# bandswitch.net
KiCad netlist of a schematic drawn in EAGLE
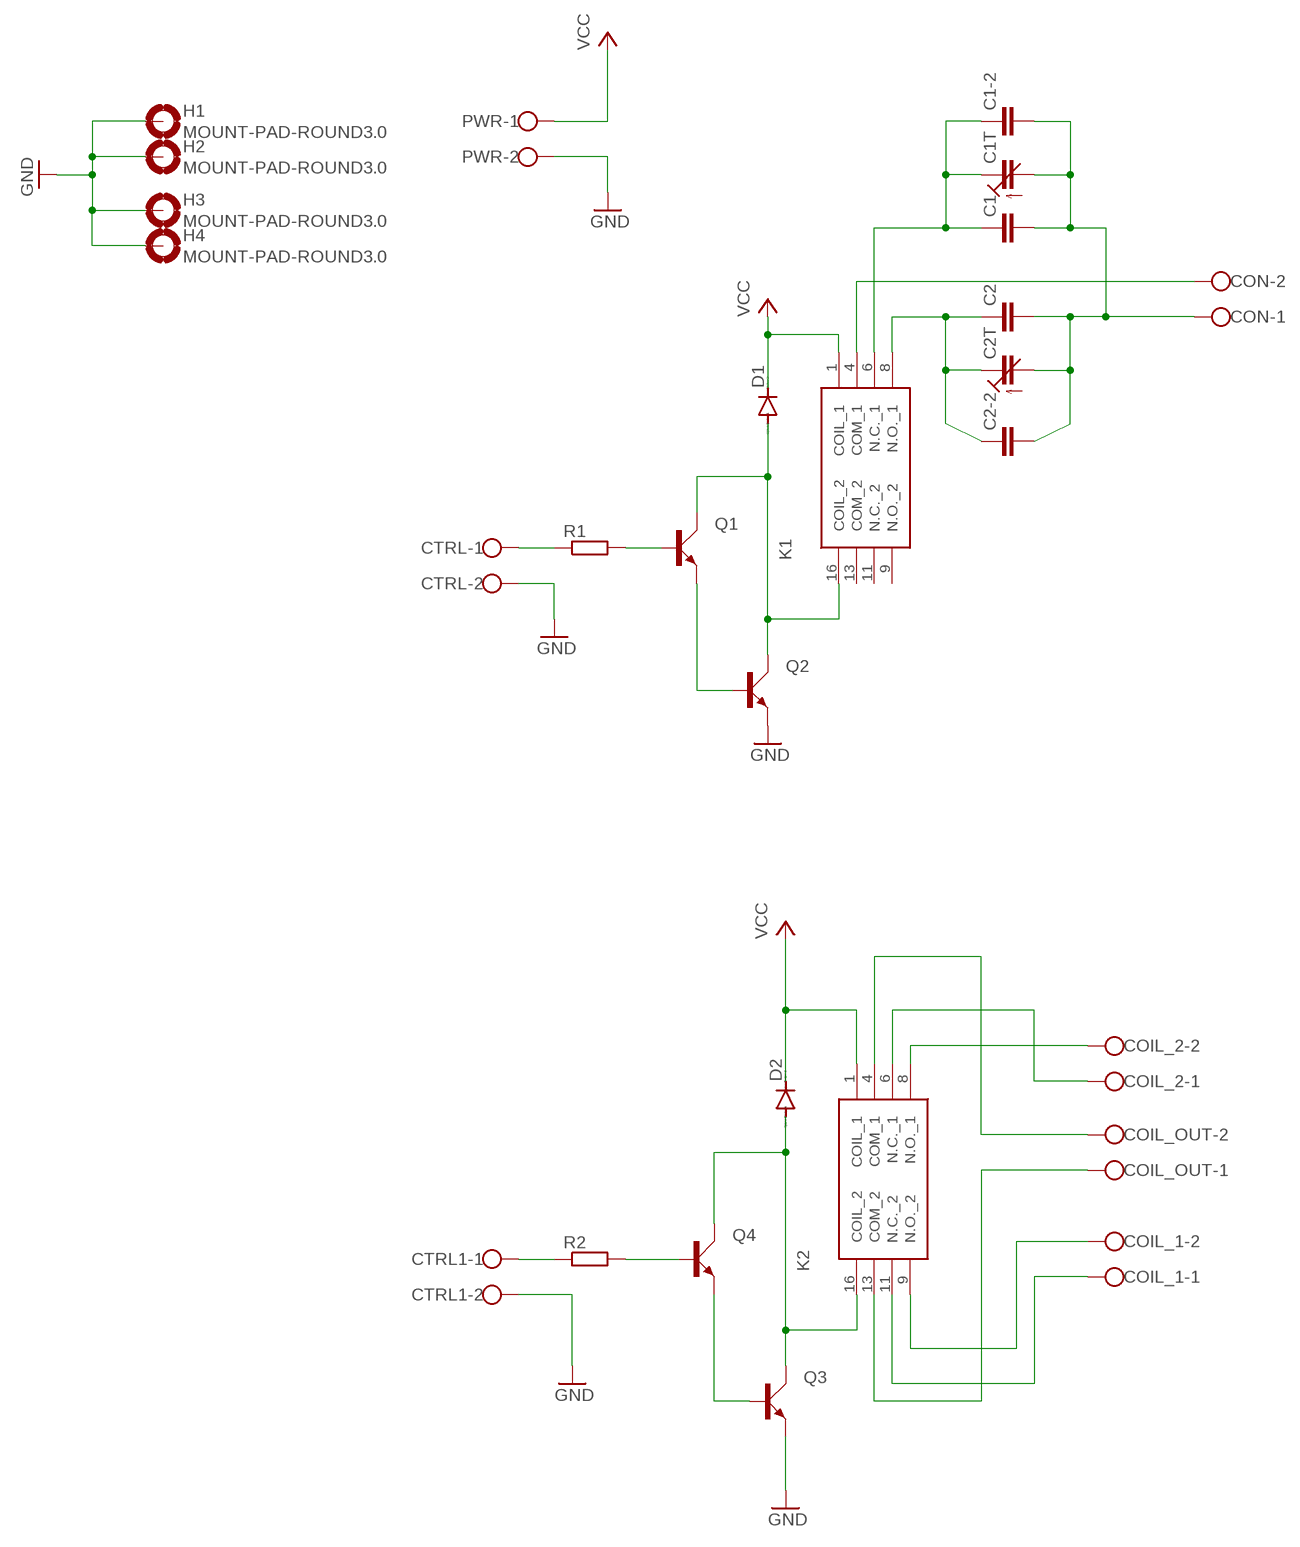
[diagram p0: schematic, sheet 1]

(export (version "E")
  (design (tool "Eeschema 10.0.6"))
  (components
    (comp (ref "C1")
      (value "C_0805_PTH")
      (footprint "eagle-import:C0805K")
      (libsource (lib "eagle-import") (part "C_0805_PTH"))
    )
    (comp (ref "C1-2")
      (value "C_0805_PTH")
      (footprint "eagle-import:C0805K")
      (libsource (lib "eagle-import") (part "C_0805_PTH"))
    )
    (comp (ref "C1T")
      (value "C_TRIM_TH")
      (footprint "eagle-import:CTRIM3050.505")
      (libsource (lib "eagle-import") (part "C_TRIM_TH"))
    )
    (comp (ref "C2")
      (value "C_0805_PTH")
      (footprint "eagle-import:C0805K")
      (libsource (lib "eagle-import") (part "C_0805_PTH"))
    )
    (comp (ref "C2-2")
      (value "C_0805_PTH")
      (footprint "eagle-import:C0805K")
      (libsource (lib "eagle-import") (part "C_0805_PTH"))
    )
    (comp (ref "C2T")
      (value "C_TRIM_TH")
      (footprint "eagle-import:CTRIM3050.505")
      (libsource (lib "eagle-import") (part "C_TRIM_TH"))
    )
    (comp (ref "COIL_1")
      (value "W237-102")
      (footprint "eagle-import:W237-102")
      (fields (field (name "MPN") "237-102"))
      (libsource (lib "eagle-import") (part "W237-102"))
    )
    (comp (ref "COIL_2")
      (value "W237-102")
      (footprint "eagle-import:W237-102")
      (fields (field (name "MPN") "237-102"))
      (libsource (lib "eagle-import") (part "W237-102"))
    )
    (comp (ref "COIL_OUT")
      (value "W237-102")
      (footprint "eagle-import:W237-102")
      (fields (field (name "MPN") "237-102"))
      (libsource (lib "eagle-import") (part "W237-102"))
    )
    (comp (ref "CON")
      (value "W237-102")
      (footprint "eagle-import:W237-102")
      (fields (field (name "MPN") "237-102"))
      (libsource (lib "eagle-import") (part "W237-102"))
    )
    (comp (ref "CTRL")
      (value "W237-102")
      (footprint "eagle-import:W237-102")
      (fields (field (name "MPN") "237-102"))
      (libsource (lib "eagle-import") (part "W237-102"))
    )
    (comp (ref "CTRL1")
      (value "W237-102")
      (footprint "eagle-import:W237-102")
      (fields (field (name "MPN") "237-102"))
      (libsource (lib "eagle-import") (part "W237-102"))
    )
    (comp (ref "D1")
      (value "1N4148DO35-7")
      (footprint "eagle-import:DO35-7")
      (libsource (lib "eagle-import") (part "1N4148DO35-7"))
    )
    (comp (ref "D2")
      (value "1N4148DO35-7")
      (footprint "eagle-import:DO35-7")
      (libsource (lib "eagle-import") (part "1N4148DO35-7"))
    )
    (comp (ref "H1")
      (value "MOUNT-PAD-ROUND3.0")
      (footprint "eagle-import:3,0-PAD")
      (libsource (lib "eagle-import") (part "MOUNT-PAD-ROUND3.0"))
    )
    (comp (ref "H2")
      (value "MOUNT-PAD-ROUND3.0")
      (footprint "eagle-import:3,0-PAD")
      (libsource (lib "eagle-import") (part "MOUNT-PAD-ROUND3.0"))
    )
    (comp (ref "H3")
      (value "MOUNT-PAD-ROUND3.0")
      (footprint "eagle-import:3,0-PAD")
      (libsource (lib "eagle-import") (part "MOUNT-PAD-ROUND3.0"))
    )
    (comp (ref "H4")
      (value "MOUNT-PAD-ROUND3.0")
      (footprint "eagle-import:3,0-PAD")
      (libsource (lib "eagle-import") (part "MOUNT-PAD-ROUND3.0"))
    )
    (comp (ref "K1")
      (value "G5V-2-H1-DC5")
      (footprint "eagle-import:G5V2H1DC5")
      (fields (field (name "MOUSER_PART_NUMBER") "653-G5V-2-H1-DC5"))
      (libsource (lib "eagle-import") (part "G5V-2-H1-DC5"))
    )
    (comp (ref "K2")
      (value "G5V-2-H1-DC5")
      (footprint "eagle-import:G5V2H1DC5")
      (fields (field (name "MOUSER_PART_NUMBER") "653-G5V-2-H1-DC5"))
      (libsource (lib "eagle-import") (part "G5V-2-H1-DC5"))
    )
    (comp (ref "PWR")
      (value "W237-102")
      (footprint "eagle-import:W237-102")
      (fields (field (name "MPN") "237-102"))
      (libsource (lib "eagle-import") (part "W237-102"))
    )
    (comp (ref "Q1")
      (value "BC547")
      (footprint "eagle-import:SOT54A")
      (libsource (lib "eagle-import") (part "BC547"))
    )
    (comp (ref "Q2")
      (value "BC547")
      (footprint "eagle-import:SOT54A")
      (libsource (lib "eagle-import") (part "BC547"))
    )
    (comp (ref "Q3")
      (value "BC547")
      (footprint "eagle-import:SOT54A")
      (libsource (lib "eagle-import") (part "BC547"))
    )
    (comp (ref "Q4")
      (value "BC547")
      (footprint "eagle-import:SOT54A")
      (libsource (lib "eagle-import") (part "BC547"))
    )
    (comp (ref "R1")
      (value "R_0805_PTH")
      (footprint "eagle-import:R0805")
      (libsource (lib "eagle-import") (part "R_0805_PTH"))
    )
    (comp (ref "R2")
      (value "R_0805_PTH")
      (footprint "eagle-import:R0805")
      (libsource (lib "eagle-import") (part "R_0805_PTH"))
    )
  )
  (nets
    (net (code "1") (name "GND") (class "Default")
      (node (ref "CTRL") (pin "2") (pinfunction "KL_2") (pintype "passive"))
      (node (ref "CTRL1") (pin "2") (pinfunction "KL_2") (pintype "passive"))
      (node (ref "H1") (pin "B3,0") (pinfunction "MOUNT_B3,0") (pintype "passive"))
      (node (ref "H2") (pin "B3,0") (pinfunction "MOUNT_B3,0") (pintype "passive"))
      (node (ref "H3") (pin "B3,0") (pinfunction "MOUNT_B3,0") (pintype "passive"))
      (node (ref "H4") (pin "B3,0") (pinfunction "MOUNT_B3,0") (pintype "passive"))
      (node (ref "PWR") (pin "2") (pinfunction "KL_2") (pintype "passive"))
      (node (ref "Q2") (pin "E") (pinfunction "E_E") (pintype "passive"))
      (node (ref "Q3") (pin "E") (pinfunction "E_E") (pintype "passive"))
    )
    (net (code "2") (name "Net-(C1T-A)") (class "Default")
      (node (ref "C1") (pin "2") (pinfunction "2_2") (pintype "passive"))
      (node (ref "C1") (pin "P$2") (pinfunction "2_P$2") (pintype "passive"))
      (node (ref "C1-2") (pin "2") (pinfunction "2_2") (pintype "passive"))
      (node (ref "C1-2") (pin "P$2") (pinfunction "2_P$2") (pintype "passive"))
      (node (ref "C1T") (pin "1") (pinfunction "A_1") (pintype "passive"))
      (node (ref "C2") (pin "2") (pinfunction "2_2") (pintype "passive"))
      (node (ref "C2") (pin "P$2") (pinfunction "2_P$2") (pintype "passive"))
      (node (ref "C2-2") (pin "2") (pinfunction "2_2") (pintype "passive"))
      (node (ref "C2-2") (pin "P$2") (pinfunction "2_P$2") (pintype "passive"))
      (node (ref "C2T") (pin "1") (pinfunction "A_1") (pintype "passive"))
      (node (ref "CON") (pin "1") (pinfunction "KL_1") (pintype "passive"))
    )
    (net (code "3") (name "Net-(C1T-E)") (class "Default")
      (node (ref "C1") (pin "1") (pinfunction "1_1") (pintype "passive"))
      (node (ref "C1") (pin "P$1") (pinfunction "1_P$1") (pintype "passive"))
      (node (ref "C1-2") (pin "1") (pinfunction "1_1") (pintype "passive"))
      (node (ref "C1-2") (pin "P$1") (pinfunction "1_P$1") (pintype "passive"))
      (node (ref "C1T") (pin "2") (pinfunction "E_2") (pintype "passive"))
      (node (ref "K1") (pin "6") (pinfunction "N.C._1_6") (pintype "bidirectional"))
    )
    (net (code "4") (name "Net-(C2T-E)") (class "Default")
      (node (ref "C2") (pin "1") (pinfunction "1_1") (pintype "passive"))
      (node (ref "C2") (pin "P$1") (pinfunction "1_P$1") (pintype "passive"))
      (node (ref "C2-2") (pin "1") (pinfunction "1_1") (pintype "passive"))
      (node (ref "C2-2") (pin "P$1") (pinfunction "1_P$1") (pintype "passive"))
      (node (ref "C2T") (pin "2") (pinfunction "E_2") (pintype "passive"))
      (node (ref "K1") (pin "8") (pinfunction "N.O._1_8") (pintype "bidirectional"))
    )
    (net (code "5") (name "Net-(COIL_1A-KL)") (class "Default")
      (node (ref "COIL_1") (pin "1") (pinfunction "KL_1") (pintype "passive"))
      (node (ref "K2") (pin "11") (pinfunction "N.C._2_11") (pintype "bidirectional"))
    )
    (net (code "6") (name "Net-(COIL_1B-KL)") (class "Default")
      (node (ref "COIL_1") (pin "2") (pinfunction "KL_2") (pintype "passive"))
      (node (ref "K2") (pin "9") (pinfunction "N.O._2_9") (pintype "bidirectional"))
    )
    (net (code "7") (name "Net-(COIL_2A-KL)") (class "Default")
      (node (ref "COIL_2") (pin "1") (pinfunction "KL_1") (pintype "passive"))
      (node (ref "K2") (pin "6") (pinfunction "N.C._1_6") (pintype "bidirectional"))
    )
    (net (code "8") (name "Net-(COIL_2B-KL)") (class "Default")
      (node (ref "COIL_2") (pin "2") (pinfunction "KL_2") (pintype "passive"))
      (node (ref "K2") (pin "8") (pinfunction "N.O._1_8") (pintype "bidirectional"))
    )
    (net (code "9") (name "Net-(COIL_OUTA-KL)") (class "Default")
      (node (ref "COIL_OUT") (pin "1") (pinfunction "KL_1") (pintype "passive"))
      (node (ref "K2") (pin "13") (pinfunction "COM_2_13") (pintype "bidirectional"))
    )
    (net (code "10") (name "Net-(COIL_OUTB-KL)") (class "Default")
      (node (ref "COIL_OUT") (pin "2") (pinfunction "KL_2") (pintype "passive"))
      (node (ref "K2") (pin "4") (pinfunction "COM_1_4") (pintype "bidirectional"))
    )
    (net (code "11") (name "Net-(CONB-KL)") (class "Default")
      (node (ref "CON") (pin "2") (pinfunction "KL_2") (pintype "passive"))
      (node (ref "K1") (pin "4") (pinfunction "COM_1_4") (pintype "bidirectional"))
    )
    (net (code "12") (name "Net-(CTRL1A-KL)") (class "Default")
      (node (ref "CTRL1") (pin "1") (pinfunction "KL_1") (pintype "passive"))
      (node (ref "R2") (pin "1") (pinfunction "1_1") (pintype "passive"))
      (node (ref "R2") (pin "P$1") (pinfunction "1_P$1") (pintype "passive"))
    )
    (net (code "13") (name "Net-(CTRLA-KL)") (class "Default")
      (node (ref "CTRL") (pin "1") (pinfunction "KL_1") (pintype "passive"))
      (node (ref "R1") (pin "1") (pinfunction "1_1") (pintype "passive"))
      (node (ref "R1") (pin "P$1") (pinfunction "1_P$1") (pintype "passive"))
    )
    (net (code "14") (name "Net-(K1-COIL_2)") (class "Default")
      (node (ref "D1") (pin "A") (pinfunction "A_A") (pintype "passive"))
      (node (ref "K1") (pin "16") (pinfunction "COIL_2_16") (pintype "bidirectional"))
      (node (ref "Q1") (pin "C") (pinfunction "C_C") (pintype "passive"))
      (node (ref "Q2") (pin "C") (pinfunction "C_C") (pintype "passive"))
    )
    (net (code "15") (name "Net-(K2-COIL_2)") (class "Default")
      (node (ref "D2") (pin "A") (pinfunction "A_A") (pintype "passive"))
      (node (ref "K2") (pin "16") (pinfunction "COIL_2_16") (pintype "bidirectional"))
      (node (ref "Q3") (pin "C") (pinfunction "C_C") (pintype "passive"))
      (node (ref "Q4") (pin "C") (pinfunction "C_C") (pintype "passive"))
    )
    (net (code "16") (name "Net-(Q1-PadB)") (class "Default")
      (node (ref "Q1") (pin "B") (pinfunction "B_B") (pintype "passive"))
      (node (ref "R1") (pin "2") (pinfunction "2_2") (pintype "passive"))
      (node (ref "R1") (pin "P$2") (pinfunction "2_P$2") (pintype "passive"))
    )
    (net (code "17") (name "Net-(Q1-PadE)") (class "Default")
      (node (ref "Q1") (pin "E") (pinfunction "E_E") (pintype "passive"))
      (node (ref "Q2") (pin "B") (pinfunction "B_B") (pintype "passive"))
    )
    (net (code "18") (name "Net-(Q3-PadB)") (class "Default")
      (node (ref "Q3") (pin "B") (pinfunction "B_B") (pintype "passive"))
      (node (ref "Q4") (pin "E") (pinfunction "E_E") (pintype "passive"))
    )
    (net (code "19") (name "Net-(Q4-PadB)") (class "Default")
      (node (ref "Q4") (pin "B") (pinfunction "B_B") (pintype "passive"))
      (node (ref "R2") (pin "2") (pinfunction "2_2") (pintype "passive"))
      (node (ref "R2") (pin "P$2") (pinfunction "2_P$2") (pintype "passive"))
    )
    (net (code "20") (name "VCC") (class "Default")
      (node (ref "D1") (pin "C") (pinfunction "C_C") (pintype "passive"))
      (node (ref "D2") (pin "C") (pinfunction "C_C") (pintype "passive"))
      (node (ref "K1") (pin "1") (pinfunction "COIL_1_1") (pintype "bidirectional"))
      (node (ref "K2") (pin "1") (pinfunction "COIL_1_1") (pintype "bidirectional"))
      (node (ref "PWR") (pin "1") (pinfunction "KL_1") (pintype "passive"))
    )
    (net (code "21") (name "unconnected-(K1-COM_2-Pad13)") (class "Default")
      (node (ref "K1") (pin "13") (pinfunction "COM_2_13") (pintype "bidirectional"))
    )
    (net (code "22") (name "unconnected-(K1-N.C._2-Pad11)") (class "Default")
      (node (ref "K1") (pin "11") (pinfunction "N.C._2_11") (pintype "bidirectional"))
    )
    (net (code "23") (name "unconnected-(K1-N.O._2-Pad9)") (class "Default")
      (node (ref "K1") (pin "9") (pinfunction "N.O._2_9") (pintype "bidirectional"))
    )
  )
)
